# sensores_y_actuadores.net
KiCad netlist of a schematic drawn in EAGLE
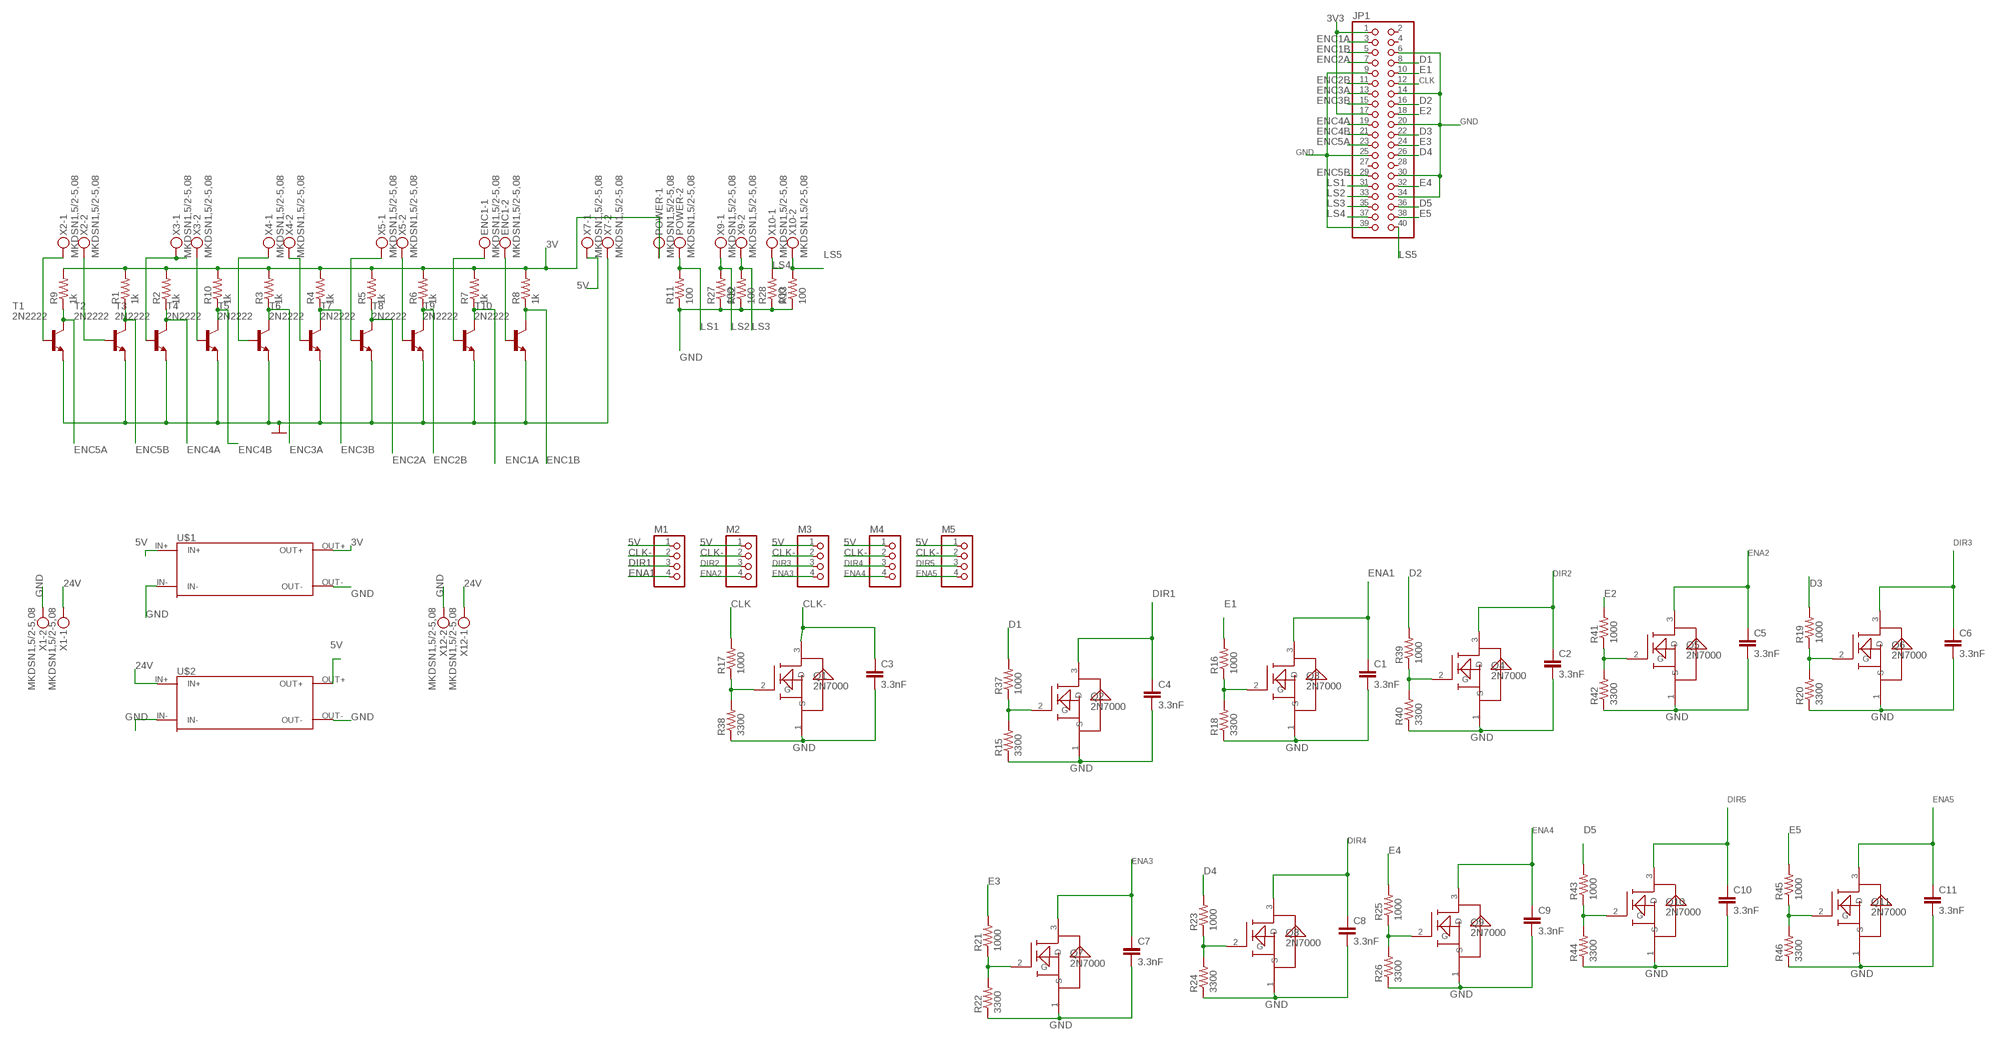
[diagram p0: schematic, sheet 1]

(export (version "E")
  (design (tool "Eeschema 10.0.6"))
  (components
    (comp (ref "C1")
      (value "3.3nF")
      (footprint "eagle-import:C025-024X044")
      (libsource (lib "eagle-import") (part "C-EU025-024X044"))
    )
    (comp (ref "C2")
      (value "3.3nF")
      (footprint "eagle-import:C025-024X044")
      (libsource (lib "eagle-import") (part "C-EU025-024X044"))
    )
    (comp (ref "C3")
      (value "3.3nF")
      (footprint "eagle-import:C025-024X044")
      (libsource (lib "eagle-import") (part "C-EU025-024X044"))
    )
    (comp (ref "C4")
      (value "3.3nF")
      (footprint "eagle-import:C025-024X044")
      (libsource (lib "eagle-import") (part "C-EU025-024X044"))
    )
    (comp (ref "C5")
      (value "3.3nF")
      (footprint "eagle-import:C025-024X044")
      (libsource (lib "eagle-import") (part "C-EU025-024X044"))
    )
    (comp (ref "C6")
      (value "3.3nF")
      (footprint "eagle-import:C025-024X044")
      (libsource (lib "eagle-import") (part "C-EU025-024X044"))
    )
    (comp (ref "C7")
      (value "3.3nF")
      (footprint "eagle-import:C025-024X044")
      (libsource (lib "eagle-import") (part "C-EU025-024X044"))
    )
    (comp (ref "C8")
      (value "3.3nF")
      (footprint "eagle-import:C025-024X044")
      (libsource (lib "eagle-import") (part "C-EU025-024X044"))
    )
    (comp (ref "C9")
      (value "3.3nF")
      (footprint "eagle-import:C025-024X044")
      (libsource (lib "eagle-import") (part "C-EU025-024X044"))
    )
    (comp (ref "C10")
      (value "3.3nF")
      (footprint "eagle-import:C025-024X044")
      (libsource (lib "eagle-import") (part "C-EU025-024X044"))
    )
    (comp (ref "C11")
      (value "3.3nF")
      (footprint "eagle-import:C025-024X044")
      (libsource (lib "eagle-import") (part "C-EU025-024X044"))
    )
    (comp (ref "ENC1")
      (value "MKDSN1,5/2-5,08")
      (footprint "eagle-import:MKDSN1,5_2-5,08")
      (libsource (lib "eagle-import") (part "MKDSN1,5/2-5,08"))
    )
    (comp (ref "JP1")
      (value "PINHD-2X20")
      (footprint "eagle-import:2X20")
      (libsource (lib "eagle-import") (part "PINHD-2X20"))
    )
    (comp (ref "M1")
      (value "PINHD-1X4")
      (footprint "eagle-import:1X04")
      (libsource (lib "eagle-import") (part "PINHD-1X4"))
    )
    (comp (ref "M2")
      (value "PINHD-1X4")
      (footprint "eagle-import:1X04")
      (libsource (lib "eagle-import") (part "PINHD-1X4"))
    )
    (comp (ref "M3")
      (value "PINHD-1X4")
      (footprint "eagle-import:1X04")
      (libsource (lib "eagle-import") (part "PINHD-1X4"))
    )
    (comp (ref "M4")
      (value "PINHD-1X4")
      (footprint "eagle-import:1X04")
      (libsource (lib "eagle-import") (part "PINHD-1X4"))
    )
    (comp (ref "M5")
      (value "PINHD-1X4")
      (footprint "eagle-import:1X04")
      (libsource (lib "eagle-import") (part "PINHD-1X4"))
    )
    (comp (ref "POWER")
      (value "MKDSN1,5/2-5,08")
      (footprint "eagle-import:MKDSN1,5_2-5,08")
      (libsource (lib "eagle-import") (part "MKDSN1,5/2-5,08"))
    )
    (comp (ref "Q1")
      (value "2N7000")
      (footprint "eagle-import:2N7000")
      (libsource (lib "eagle-import") (part "2N7000"))
    )
    (comp (ref "Q2")
      (value "2N7000")
      (footprint "eagle-import:2N7000")
      (libsource (lib "eagle-import") (part "2N7000"))
    )
    (comp (ref "Q3")
      (value "2N7000")
      (footprint "eagle-import:2N7000")
      (libsource (lib "eagle-import") (part "2N7000"))
    )
    (comp (ref "Q4")
      (value "2N7000")
      (footprint "eagle-import:2N7000")
      (libsource (lib "eagle-import") (part "2N7000"))
    )
    (comp (ref "Q5")
      (value "2N7000")
      (footprint "eagle-import:2N7000")
      (libsource (lib "eagle-import") (part "2N7000"))
    )
    (comp (ref "Q6")
      (value "2N7000")
      (footprint "eagle-import:2N7000")
      (libsource (lib "eagle-import") (part "2N7000"))
    )
    (comp (ref "Q7")
      (value "2N7000")
      (footprint "eagle-import:2N7000")
      (libsource (lib "eagle-import") (part "2N7000"))
    )
    (comp (ref "Q8")
      (value "2N7000")
      (footprint "eagle-import:2N7000")
      (libsource (lib "eagle-import") (part "2N7000"))
    )
    (comp (ref "Q9")
      (value "2N7000")
      (footprint "eagle-import:2N7000")
      (libsource (lib "eagle-import") (part "2N7000"))
    )
    (comp (ref "Q10")
      (value "2N7000")
      (footprint "eagle-import:2N7000")
      (libsource (lib "eagle-import") (part "2N7000"))
    )
    (comp (ref "Q11")
      (value "2N7000")
      (footprint "eagle-import:2N7000")
      (libsource (lib "eagle-import") (part "2N7000"))
    )
    (comp (ref "R1")
      (value "1k")
      (footprint "eagle-import:0207_10")
      (libsource (lib "eagle-import") (part "R-US_0207/10"))
    )
    (comp (ref "R2")
      (value "1k")
      (footprint "eagle-import:0207_10")
      (libsource (lib "eagle-import") (part "R-US_0207/10"))
    )
    (comp (ref "R3")
      (value "1k")
      (footprint "eagle-import:0207_10")
      (libsource (lib "eagle-import") (part "R-US_0207/10"))
    )
    (comp (ref "R4")
      (value "1k")
      (footprint "eagle-import:0207_10")
      (libsource (lib "eagle-import") (part "R-US_0207/10"))
    )
    (comp (ref "R5")
      (value "1k")
      (footprint "eagle-import:0207_10")
      (libsource (lib "eagle-import") (part "R-US_0207/10"))
    )
    (comp (ref "R6")
      (value "1k")
      (footprint "eagle-import:0207_10")
      (libsource (lib "eagle-import") (part "R-US_0207/10"))
    )
    (comp (ref "R7")
      (value "1k")
      (footprint "eagle-import:0207_10")
      (libsource (lib "eagle-import") (part "R-US_0207/10"))
    )
    (comp (ref "R8")
      (value "1k")
      (footprint "eagle-import:0207_10")
      (libsource (lib "eagle-import") (part "R-US_0207/10"))
    )
    (comp (ref "R9")
      (value "1k")
      (footprint "eagle-import:0207_10")
      (libsource (lib "eagle-import") (part "R-US_0207/10"))
    )
    (comp (ref "R10")
      (value "1k")
      (footprint "eagle-import:0207_10")
      (libsource (lib "eagle-import") (part "R-US_0207/10"))
    )
    (comp (ref "R11")
      (value "100")
      (footprint "eagle-import:0207_10")
      (libsource (lib "eagle-import") (part "R-US_0207/10"))
    )
    (comp (ref "R12")
      (value "100")
      (footprint "eagle-import:0207_10")
      (libsource (lib "eagle-import") (part "R-US_0207/10"))
    )
    (comp (ref "R13")
      (value "100")
      (footprint "eagle-import:0207_10")
      (libsource (lib "eagle-import") (part "R-US_0207/10"))
    )
    (comp (ref "R15")
      (value "3300")
      (footprint "eagle-import:0207_10")
      (libsource (lib "eagle-import") (part "R-US_0207/10"))
    )
    (comp (ref "R16")
      (value "1000")
      (footprint "eagle-import:0207_10")
      (libsource (lib "eagle-import") (part "R-US_0207/10"))
    )
    (comp (ref "R17")
      (value "1000")
      (footprint "eagle-import:0207_10")
      (libsource (lib "eagle-import") (part "R-US_0207/10"))
    )
    (comp (ref "R18")
      (value "3300")
      (footprint "eagle-import:0207_10")
      (libsource (lib "eagle-import") (part "R-US_0207/10"))
    )
    (comp (ref "R19")
      (value "1000")
      (footprint "eagle-import:0207_10")
      (libsource (lib "eagle-import") (part "R-US_0207/10"))
    )
    (comp (ref "R20")
      (value "3300")
      (footprint "eagle-import:0207_10")
      (libsource (lib "eagle-import") (part "R-US_0207/10"))
    )
    (comp (ref "R21")
      (value "1000")
      (footprint "eagle-import:0207_10")
      (libsource (lib "eagle-import") (part "R-US_0207/10"))
    )
    (comp (ref "R22")
      (value "3300")
      (footprint "eagle-import:0207_10")
      (libsource (lib "eagle-import") (part "R-US_0207/10"))
    )
    (comp (ref "R23")
      (value "1000")
      (footprint "eagle-import:0207_10")
      (libsource (lib "eagle-import") (part "R-US_0207/10"))
    )
    (comp (ref "R24")
      (value "3300")
      (footprint "eagle-import:0207_10")
      (libsource (lib "eagle-import") (part "R-US_0207/10"))
    )
    (comp (ref "R25")
      (value "1000")
      (footprint "eagle-import:0207_10")
      (libsource (lib "eagle-import") (part "R-US_0207/10"))
    )
    (comp (ref "R26")
      (value "3300")
      (footprint "eagle-import:0207_10")
      (libsource (lib "eagle-import") (part "R-US_0207/10"))
    )
    (comp (ref "R27")
      (value "100")
      (footprint "eagle-import:0207_10")
      (libsource (lib "eagle-import") (part "R-US_0207/10"))
    )
    (comp (ref "R28")
      (value "100")
      (footprint "eagle-import:0207_10")
      (libsource (lib "eagle-import") (part "R-US_0207/10"))
    )
    (comp (ref "R37")
      (value "1000")
      (footprint "eagle-import:0207_10")
      (libsource (lib "eagle-import") (part "R-US_0207/10"))
    )
    (comp (ref "R38")
      (value "3300")
      (footprint "eagle-import:0207_10")
      (libsource (lib "eagle-import") (part "R-US_0207/10"))
    )
    (comp (ref "R39")
      (value "1000")
      (footprint "eagle-import:0207_10")
      (libsource (lib "eagle-import") (part "R-US_0207/10"))
    )
    (comp (ref "R40")
      (value "3300")
      (footprint "eagle-import:0207_10")
      (libsource (lib "eagle-import") (part "R-US_0207/10"))
    )
    (comp (ref "R41")
      (value "1000")
      (footprint "eagle-import:0207_10")
      (libsource (lib "eagle-import") (part "R-US_0207/10"))
    )
    (comp (ref "R42")
      (value "3300")
      (footprint "eagle-import:0207_10")
      (libsource (lib "eagle-import") (part "R-US_0207/10"))
    )
    (comp (ref "R43")
      (value "1000")
      (footprint "eagle-import:0207_10")
      (libsource (lib "eagle-import") (part "R-US_0207/10"))
    )
    (comp (ref "R44")
      (value "3300")
      (footprint "eagle-import:0207_10")
      (libsource (lib "eagle-import") (part "R-US_0207/10"))
    )
    (comp (ref "R45")
      (value "1000")
      (footprint "eagle-import:0207_10")
      (libsource (lib "eagle-import") (part "R-US_0207/10"))
    )
    (comp (ref "R46")
      (value "3300")
      (footprint "eagle-import:0207_10")
      (libsource (lib "eagle-import") (part "R-US_0207/10"))
    )
    (comp (ref "T1")
      (value "2N2222")
      (footprint "eagle-import:2N2222")
      (libsource (lib "eagle-import") (part "2N2222"))
    )
    (comp (ref "T2")
      (value "2N2222")
      (footprint "eagle-import:2N2222")
      (libsource (lib "eagle-import") (part "2N2222"))
    )
    (comp (ref "T3")
      (value "2N2222")
      (footprint "eagle-import:2N2222")
      (libsource (lib "eagle-import") (part "2N2222"))
    )
    (comp (ref "T4")
      (value "2N2222")
      (footprint "eagle-import:2N2222")
      (libsource (lib "eagle-import") (part "2N2222"))
    )
    (comp (ref "T5")
      (value "2N2222")
      (footprint "eagle-import:2N2222")
      (libsource (lib "eagle-import") (part "2N2222"))
    )
    (comp (ref "T6")
      (value "2N2222")
      (footprint "eagle-import:2N2222")
      (libsource (lib "eagle-import") (part "2N2222"))
    )
    (comp (ref "T7")
      (value "2N2222")
      (footprint "eagle-import:2N2222")
      (libsource (lib "eagle-import") (part "2N2222"))
    )
    (comp (ref "T8")
      (value "2N2222")
      (footprint "eagle-import:2N2222")
      (libsource (lib "eagle-import") (part "2N2222"))
    )
    (comp (ref "T9")
      (value "2N2222")
      (footprint "eagle-import:2N2222")
      (libsource (lib "eagle-import") (part "2N2222"))
    )
    (comp (ref "T10")
      (value "2N2222")
      (footprint "eagle-import:2N2222")
      (libsource (lib "eagle-import") (part "2N2222"))
    )
    (comp (ref "U$1")
      (value "LM2596")
      (footprint "eagle-import:LM2596")
      (libsource (lib "eagle-import") (part "LM2596"))
    )
    (comp (ref "U$2")
      (value "LM2596")
      (footprint "eagle-import:LM2596")
      (libsource (lib "eagle-import") (part "LM2596"))
    )
    (comp (ref "X1")
      (value "MKDSN1,5/2-5,08")
      (footprint "eagle-import:MKDSN1,5_2-5,08")
      (libsource (lib "eagle-import") (part "MKDSN1,5/2-5,08"))
    )
    (comp (ref "X2")
      (value "MKDSN1,5/2-5,08")
      (footprint "eagle-import:MKDSN1,5_2-5,08")
      (libsource (lib "eagle-import") (part "MKDSN1,5/2-5,08"))
    )
    (comp (ref "X3")
      (value "MKDSN1,5/2-5,08")
      (footprint "eagle-import:MKDSN1,5_2-5,08")
      (libsource (lib "eagle-import") (part "MKDSN1,5/2-5,08"))
    )
    (comp (ref "X4")
      (value "MKDSN1,5/2-5,08")
      (footprint "eagle-import:MKDSN1,5_2-5,08")
      (libsource (lib "eagle-import") (part "MKDSN1,5/2-5,08"))
    )
    (comp (ref "X5")
      (value "MKDSN1,5/2-5,08")
      (footprint "eagle-import:MKDSN1,5_2-5,08")
      (libsource (lib "eagle-import") (part "MKDSN1,5/2-5,08"))
    )
    (comp (ref "X7")
      (value "MKDSN1,5/2-5,08")
      (footprint "eagle-import:MKDSN1,5_2-5,08")
      (libsource (lib "eagle-import") (part "MKDSN1,5/2-5,08"))
    )
    (comp (ref "X9")
      (value "MKDSN1,5/2-5,08")
      (footprint "eagle-import:MKDSN1,5_2-5,08")
      (libsource (lib "eagle-import") (part "MKDSN1,5/2-5,08"))
    )
    (comp (ref "X10")
      (value "MKDSN1,5/2-5,08")
      (footprint "eagle-import:MKDSN1,5_2-5,08")
      (libsource (lib "eagle-import") (part "MKDSN1,5/2-5,08"))
    )
    (comp (ref "X12")
      (value "MKDSN1,5/2-5,08")
      (footprint "eagle-import:MKDSN1,5_2-5,08")
      (libsource (lib "eagle-import") (part "MKDSN1,5/2-5,08"))
    )
  )
  (nets
    (net (code "1") (name "/3V") (class "Default")
      (node (ref "POWER") (pin "1") (pinfunction "KL_1") (pintype "passive"))
      (node (ref "R1") (pin "2") (pinfunction "2_2") (pintype "passive"))
      (node (ref "R10") (pin "2") (pinfunction "2_2") (pintype "passive"))
      (node (ref "R2") (pin "2") (pinfunction "2_2") (pintype "passive"))
      (node (ref "R3") (pin "2") (pinfunction "2_2") (pintype "passive"))
      (node (ref "R4") (pin "2") (pinfunction "2_2") (pintype "passive"))
      (node (ref "R5") (pin "2") (pinfunction "2_2") (pintype "passive"))
      (node (ref "R6") (pin "2") (pinfunction "2_2") (pintype "passive"))
      (node (ref "R7") (pin "2") (pinfunction "2_2") (pintype "passive"))
      (node (ref "R8") (pin "2") (pinfunction "2_2") (pintype "passive"))
      (node (ref "R9") (pin "2") (pinfunction "2_2") (pintype "passive"))
      (node (ref "U$1") (pin "OUT+") (pinfunction "OUT+_OUT+") (pintype "bidirectional"))
    )
    (net (code "2") (name "/3V3") (class "Default")
      (node (ref "JP1") (pin "1") (pinfunction "1_1") (pintype "passive"))
      (node (ref "JP1") (pin "17") (pinfunction "17_17") (pintype "passive"))
    )
    (net (code "3") (name "/5V") (class "Default")
      (node (ref "M1") (pin "1") (pinfunction "1_1") (pintype "passive"))
      (node (ref "M2") (pin "1") (pinfunction "1_1") (pintype "passive"))
      (node (ref "M3") (pin "1") (pinfunction "1_1") (pintype "passive"))
      (node (ref "M4") (pin "1") (pinfunction "1_1") (pintype "passive"))
      (node (ref "M5") (pin "1") (pinfunction "1_1") (pintype "passive"))
      (node (ref "U$1") (pin "IN+") (pinfunction "IN+_IN+") (pintype "bidirectional"))
      (node (ref "U$2") (pin "OUT+") (pinfunction "OUT+_OUT+") (pintype "bidirectional"))
      (node (ref "X7") (pin "1") (pinfunction "KL_1") (pintype "passive"))
    )
    (net (code "4") (name "/24V") (class "Default")
      (node (ref "U$2") (pin "IN+") (pinfunction "IN+_IN+") (pintype "bidirectional"))
      (node (ref "X1") (pin "1") (pinfunction "KL_1") (pintype "passive"))
      (node (ref "X12") (pin "1") (pinfunction "KL_1") (pintype "passive"))
    )
    (net (code "5") (name "/CLK") (class "Default")
      (node (ref "JP1") (pin "12") (pinfunction "12_12") (pintype "passive"))
      (node (ref "R17") (pin "2") (pinfunction "2_2") (pintype "passive"))
    )
    (net (code "6") (name "/CLK-") (class "Default")
      (node (ref "C3") (pin "1") (pinfunction "1_1") (pintype "passive"))
      (node (ref "M1") (pin "2") (pinfunction "2_2") (pintype "passive"))
      (node (ref "M2") (pin "2") (pinfunction "2_2") (pintype "passive"))
      (node (ref "M3") (pin "2") (pinfunction "2_2") (pintype "passive"))
      (node (ref "M4") (pin "2") (pinfunction "2_2") (pintype "passive"))
      (node (ref "M5") (pin "2") (pinfunction "2_2") (pintype "passive"))
      (node (ref "Q1") (pin "3") (pinfunction "D_3") (pintype "bidirectional"))
    )
    (net (code "7") (name "/D1") (class "Default")
      (node (ref "JP1") (pin "8") (pinfunction "8_8") (pintype "passive"))
      (node (ref "R37") (pin "2") (pinfunction "2_2") (pintype "passive"))
    )
    (net (code "8") (name "/D2") (class "Default")
      (node (ref "JP1") (pin "16") (pinfunction "16_16") (pintype "passive"))
      (node (ref "R39") (pin "2") (pinfunction "2_2") (pintype "passive"))
    )
    (net (code "9") (name "/D3") (class "Default")
      (node (ref "JP1") (pin "22") (pinfunction "22_22") (pintype "passive"))
      (node (ref "R19") (pin "2") (pinfunction "2_2") (pintype "passive"))
    )
    (net (code "10") (name "/D4") (class "Default")
      (node (ref "JP1") (pin "26") (pinfunction "26_26") (pintype "passive"))
      (node (ref "R23") (pin "2") (pinfunction "2_2") (pintype "passive"))
    )
    (net (code "11") (name "/D5") (class "Default")
      (node (ref "JP1") (pin "36") (pinfunction "36_36") (pintype "passive"))
      (node (ref "R43") (pin "2") (pinfunction "2_2") (pintype "passive"))
    )
    (net (code "12") (name "/DIR1") (class "Default")
      (node (ref "C4") (pin "1") (pinfunction "1_1") (pintype "passive"))
      (node (ref "M1") (pin "3") (pinfunction "3_3") (pintype "passive"))
      (node (ref "Q2") (pin "3") (pinfunction "D_3") (pintype "bidirectional"))
    )
    (net (code "13") (name "/DIR2") (class "Default")
      (node (ref "C2") (pin "1") (pinfunction "1_1") (pintype "passive"))
      (node (ref "M2") (pin "3") (pinfunction "3_3") (pintype "passive"))
      (node (ref "Q4") (pin "3") (pinfunction "D_3") (pintype "bidirectional"))
    )
    (net (code "14") (name "/DIR3") (class "Default")
      (node (ref "C6") (pin "1") (pinfunction "1_1") (pintype "passive"))
      (node (ref "M3") (pin "3") (pinfunction "3_3") (pintype "passive"))
      (node (ref "Q6") (pin "3") (pinfunction "D_3") (pintype "bidirectional"))
    )
    (net (code "15") (name "/DIR4") (class "Default")
      (node (ref "C8") (pin "1") (pinfunction "1_1") (pintype "passive"))
      (node (ref "M4") (pin "3") (pinfunction "3_3") (pintype "passive"))
      (node (ref "Q8") (pin "3") (pinfunction "D_3") (pintype "bidirectional"))
    )
    (net (code "16") (name "/DIR5") (class "Default")
      (node (ref "C10") (pin "1") (pinfunction "1_1") (pintype "passive"))
      (node (ref "M5") (pin "3") (pinfunction "3_3") (pintype "passive"))
      (node (ref "Q10") (pin "3") (pinfunction "D_3") (pintype "bidirectional"))
    )
    (net (code "17") (name "/E1") (class "Default")
      (node (ref "JP1") (pin "10") (pinfunction "10_10") (pintype "passive"))
      (node (ref "R16") (pin "2") (pinfunction "2_2") (pintype "passive"))
    )
    (net (code "18") (name "/E2") (class "Default")
      (node (ref "JP1") (pin "18") (pinfunction "18_18") (pintype "passive"))
      (node (ref "R41") (pin "2") (pinfunction "2_2") (pintype "passive"))
    )
    (net (code "19") (name "/E3") (class "Default")
      (node (ref "JP1") (pin "24") (pinfunction "24_24") (pintype "passive"))
      (node (ref "R21") (pin "2") (pinfunction "2_2") (pintype "passive"))
    )
    (net (code "20") (name "/E4") (class "Default")
      (node (ref "JP1") (pin "32") (pinfunction "32_32") (pintype "passive"))
      (node (ref "R25") (pin "2") (pinfunction "2_2") (pintype "passive"))
    )
    (net (code "21") (name "/E5") (class "Default")
      (node (ref "JP1") (pin "38") (pinfunction "38_38") (pintype "passive"))
      (node (ref "R45") (pin "2") (pinfunction "2_2") (pintype "passive"))
    )
    (net (code "22") (name "/ENA1") (class "Default")
      (node (ref "C1") (pin "1") (pinfunction "1_1") (pintype "passive"))
      (node (ref "M1") (pin "4") (pinfunction "4_4") (pintype "passive"))
      (node (ref "Q3") (pin "3") (pinfunction "D_3") (pintype "bidirectional"))
    )
    (net (code "23") (name "/ENA2") (class "Default")
      (node (ref "C5") (pin "1") (pinfunction "1_1") (pintype "passive"))
      (node (ref "M2") (pin "4") (pinfunction "4_4") (pintype "passive"))
      (node (ref "Q5") (pin "3") (pinfunction "D_3") (pintype "bidirectional"))
    )
    (net (code "24") (name "/ENA3") (class "Default")
      (node (ref "C7") (pin "1") (pinfunction "1_1") (pintype "passive"))
      (node (ref "M3") (pin "4") (pinfunction "4_4") (pintype "passive"))
      (node (ref "Q7") (pin "3") (pinfunction "D_3") (pintype "bidirectional"))
    )
    (net (code "25") (name "/ENA4") (class "Default")
      (node (ref "C9") (pin "1") (pinfunction "1_1") (pintype "passive"))
      (node (ref "M4") (pin "4") (pinfunction "4_4") (pintype "passive"))
      (node (ref "Q9") (pin "3") (pinfunction "D_3") (pintype "bidirectional"))
    )
    (net (code "26") (name "/ENA5") (class "Default")
      (node (ref "C11") (pin "1") (pinfunction "1_1") (pintype "passive"))
      (node (ref "M5") (pin "4") (pinfunction "4_4") (pintype "passive"))
      (node (ref "Q11") (pin "3") (pinfunction "D_3") (pintype "bidirectional"))
    )
    (net (code "27") (name "/ENC1A") (class "Default")
      (node (ref "JP1") (pin "3") (pinfunction "3_3") (pintype "passive"))
      (node (ref "R7") (pin "1") (pinfunction "1_1") (pintype "passive"))
      (node (ref "T9") (pin "C") (pinfunction "C_C") (pintype "passive"))
    )
    (net (code "28") (name "/ENC1B") (class "Default")
      (node (ref "JP1") (pin "5") (pinfunction "5_5") (pintype "passive"))
      (node (ref "R8") (pin "1") (pinfunction "1_1") (pintype "passive"))
      (node (ref "T10") (pin "C") (pinfunction "C_C") (pintype "passive"))
    )
    (net (code "29") (name "/ENC2A") (class "Default")
      (node (ref "JP1") (pin "7") (pinfunction "7_7") (pintype "passive"))
      (node (ref "R5") (pin "1") (pinfunction "1_1") (pintype "passive"))
      (node (ref "T7") (pin "C") (pinfunction "C_C") (pintype "passive"))
    )
    (net (code "30") (name "/ENC2B") (class "Default")
      (node (ref "JP1") (pin "11") (pinfunction "11_11") (pintype "passive"))
      (node (ref "R6") (pin "1") (pinfunction "1_1") (pintype "passive"))
      (node (ref "T8") (pin "C") (pinfunction "C_C") (pintype "passive"))
    )
    (net (code "31") (name "/ENC3A") (class "Default")
      (node (ref "JP1") (pin "13") (pinfunction "13_13") (pintype "passive"))
      (node (ref "R3") (pin "1") (pinfunction "1_1") (pintype "passive"))
      (node (ref "T5") (pin "C") (pinfunction "C_C") (pintype "passive"))
    )
    (net (code "32") (name "/ENC3B") (class "Default")
      (node (ref "JP1") (pin "15") (pinfunction "15_15") (pintype "passive"))
      (node (ref "R4") (pin "1") (pinfunction "1_1") (pintype "passive"))
      (node (ref "T6") (pin "C") (pinfunction "C_C") (pintype "passive"))
    )
    (net (code "33") (name "/ENC4A") (class "Default")
      (node (ref "JP1") (pin "19") (pinfunction "19_19") (pintype "passive"))
      (node (ref "R2") (pin "1") (pinfunction "1_1") (pintype "passive"))
      (node (ref "T3") (pin "C") (pinfunction "C_C") (pintype "passive"))
    )
    (net (code "34") (name "/ENC4B") (class "Default")
      (node (ref "JP1") (pin "21") (pinfunction "21_21") (pintype "passive"))
      (node (ref "R10") (pin "1") (pinfunction "1_1") (pintype "passive"))
      (node (ref "T4") (pin "C") (pinfunction "C_C") (pintype "passive"))
    )
    (net (code "35") (name "/ENC5A") (class "Default")
      (node (ref "JP1") (pin "23") (pinfunction "23_23") (pintype "passive"))
      (node (ref "R9") (pin "1") (pinfunction "1_1") (pintype "passive"))
      (node (ref "T1") (pin "C") (pinfunction "C_C") (pintype "passive"))
    )
    (net (code "36") (name "/ENC5B") (class "Default")
      (node (ref "JP1") (pin "29") (pinfunction "29_29") (pintype "passive"))
      (node (ref "R1") (pin "1") (pinfunction "1_1") (pintype "passive"))
      (node (ref "T2") (pin "C") (pinfunction "C_C") (pintype "passive"))
    )
    (net (code "37") (name "/LS1") (class "Default")
      (node (ref "JP1") (pin "31") (pinfunction "31_31") (pintype "passive"))
      (node (ref "POWER") (pin "2") (pinfunction "KL_2") (pintype "passive"))
      (node (ref "R11") (pin "2") (pinfunction "2_2") (pintype "passive"))
    )
    (net (code "38") (name "/LS2") (class "Default")
      (node (ref "JP1") (pin "33") (pinfunction "33_33") (pintype "passive"))
      (node (ref "R27") (pin "2") (pinfunction "2_2") (pintype "passive"))
      (node (ref "X9") (pin "1") (pinfunction "KL_1") (pintype "passive"))
    )
    (net (code "39") (name "/LS3") (class "Default")
      (node (ref "JP1") (pin "35") (pinfunction "35_35") (pintype "passive"))
      (node (ref "R12") (pin "2") (pinfunction "2_2") (pintype "passive"))
      (node (ref "X9") (pin "2") (pinfunction "KL_2") (pintype "passive"))
    )
    (net (code "40") (name "/LS4") (class "Default")
      (node (ref "JP1") (pin "37") (pinfunction "37_37") (pintype "passive"))
      (node (ref "R28") (pin "2") (pinfunction "2_2") (pintype "passive"))
      (node (ref "X10") (pin "1") (pinfunction "KL_1") (pintype "passive"))
    )
    (net (code "41") (name "/LS5") (class "Default")
      (node (ref "JP1") (pin "40") (pinfunction "40_40") (pintype "passive"))
      (node (ref "R13") (pin "2") (pinfunction "2_2") (pintype "passive"))
      (node (ref "X10") (pin "2") (pinfunction "KL_2") (pintype "passive"))
    )
    (net (code "42") (name "GND") (class "Default")
      (node (ref "C1") (pin "2") (pinfunction "2_2") (pintype "passive"))
      (node (ref "C10") (pin "2") (pinfunction "2_2") (pintype "passive"))
      (node (ref "C11") (pin "2") (pinfunction "2_2") (pintype "passive"))
      (node (ref "C2") (pin "2") (pinfunction "2_2") (pintype "passive"))
      (node (ref "C3") (pin "2") (pinfunction "2_2") (pintype "passive"))
      (node (ref "C4") (pin "2") (pinfunction "2_2") (pintype "passive"))
      (node (ref "C5") (pin "2") (pinfunction "2_2") (pintype "passive"))
      (node (ref "C6") (pin "2") (pinfunction "2_2") (pintype "passive"))
      (node (ref "C7") (pin "2") (pinfunction "2_2") (pintype "passive"))
      (node (ref "C8") (pin "2") (pinfunction "2_2") (pintype "passive"))
      (node (ref "C9") (pin "2") (pinfunction "2_2") (pintype "passive"))
      (node (ref "JP1") (pin "14") (pinfunction "14_14") (pintype "passive"))
      (node (ref "JP1") (pin "20") (pinfunction "20_20") (pintype "passive"))
      (node (ref "JP1") (pin "25") (pinfunction "25_25") (pintype "passive"))
      (node (ref "JP1") (pin "30") (pinfunction "30_30") (pintype "passive"))
      (node (ref "JP1") (pin "34") (pinfunction "34_34") (pintype "passive"))
      (node (ref "JP1") (pin "39") (pinfunction "39_39") (pintype "passive"))
      (node (ref "JP1") (pin "6") (pinfunction "6_6") (pintype "passive"))
      (node (ref "JP1") (pin "9") (pinfunction "9_9") (pintype "passive"))
      (node (ref "Q1") (pin "1") (pinfunction "S_1") (pintype "bidirectional"))
      (node (ref "Q10") (pin "1") (pinfunction "S_1") (pintype "bidirectional"))
      (node (ref "Q11") (pin "1") (pinfunction "S_1") (pintype "bidirectional"))
      (node (ref "Q2") (pin "1") (pinfunction "S_1") (pintype "bidirectional"))
      (node (ref "Q3") (pin "1") (pinfunction "S_1") (pintype "bidirectional"))
      (node (ref "Q4") (pin "1") (pinfunction "S_1") (pintype "bidirectional"))
      (node (ref "Q5") (pin "1") (pinfunction "S_1") (pintype "bidirectional"))
      (node (ref "Q6") (pin "1") (pinfunction "S_1") (pintype "bidirectional"))
      (node (ref "Q7") (pin "1") (pinfunction "S_1") (pintype "bidirectional"))
      (node (ref "Q8") (pin "1") (pinfunction "S_1") (pintype "bidirectional"))
      (node (ref "Q9") (pin "1") (pinfunction "S_1") (pintype "bidirectional"))
      (node (ref "R11") (pin "1") (pinfunction "1_1") (pintype "passive"))
      (node (ref "R12") (pin "1") (pinfunction "1_1") (pintype "passive"))
      (node (ref "R13") (pin "1") (pinfunction "1_1") (pintype "passive"))
      (node (ref "R15") (pin "1") (pinfunction "1_1") (pintype "passive"))
      (node (ref "R18") (pin "1") (pinfunction "1_1") (pintype "passive"))
      (node (ref "R20") (pin "1") (pinfunction "1_1") (pintype "passive"))
      (node (ref "R22") (pin "1") (pinfunction "1_1") (pintype "passive"))
      (node (ref "R24") (pin "1") (pinfunction "1_1") (pintype "passive"))
      (node (ref "R26") (pin "1") (pinfunction "1_1") (pintype "passive"))
      (node (ref "R27") (pin "1") (pinfunction "1_1") (pintype "passive"))
      (node (ref "R28") (pin "1") (pinfunction "1_1") (pintype "passive"))
      (node (ref "R38") (pin "1") (pinfunction "1_1") (pintype "passive"))
      (node (ref "R40") (pin "1") (pinfunction "1_1") (pintype "passive"))
      (node (ref "R42") (pin "1") (pinfunction "1_1") (pintype "passive"))
      (node (ref "R44") (pin "1") (pinfunction "1_1") (pintype "passive"))
      (node (ref "R46") (pin "1") (pinfunction "1_1") (pintype "passive"))
      (node (ref "T1") (pin "E") (pinfunction "E_E") (pintype "passive"))
      (node (ref "T10") (pin "E") (pinfunction "E_E") (pintype "passive"))
      (node (ref "T2") (pin "E") (pinfunction "E_E") (pintype "passive"))
      (node (ref "T3") (pin "E") (pinfunction "E_E") (pintype "passive"))
      (node (ref "T4") (pin "E") (pinfunction "E_E") (pintype "passive"))
      (node (ref "T5") (pin "E") (pinfunction "E_E") (pintype "passive"))
      (node (ref "T6") (pin "E") (pinfunction "E_E") (pintype "passive"))
      (node (ref "T7") (pin "E") (pinfunction "E_E") (pintype "passive"))
      (node (ref "T8") (pin "E") (pinfunction "E_E") (pintype "passive"))
      (node (ref "T9") (pin "E") (pinfunction "E_E") (pintype "passive"))
      (node (ref "U$1") (pin "IN-") (pinfunction "IN-_IN-") (pintype "bidirectional"))
      (node (ref "U$1") (pin "OUT-") (pinfunction "OUT-_OUT-") (pintype "bidirectional"))
      (node (ref "U$2") (pin "IN-") (pinfunction "IN-_IN-") (pintype "bidirectional"))
      (node (ref "U$2") (pin "OUT-") (pinfunction "OUT-_OUT-") (pintype "bidirectional"))
      (node (ref "X1") (pin "2") (pinfunction "KL_2") (pintype "passive"))
      (node (ref "X12") (pin "2") (pinfunction "KL_2") (pintype "passive"))
      (node (ref "X7") (pin "2") (pinfunction "KL_2") (pintype "passive"))
    )
    (net (code "43") (name "Net-(ENC1A-KL)") (class "Default")
      (node (ref "ENC1") (pin "1") (pinfunction "KL_1") (pintype "passive"))
      (node (ref "T9") (pin "B") (pinfunction "B_B") (pintype "passive"))
    )
    (net (code "44") (name "Net-(ENC1B-KL)") (class "Default")
      (node (ref "ENC1") (pin "2") (pinfunction "KL_2") (pintype "passive"))
      (node (ref "T10") (pin "B") (pinfunction "B_B") (pintype "passive"))
    )
    (net (code "45") (name "Net-(Q1-G)") (class "Default")
      (node (ref "Q1") (pin "2") (pinfunction "G_2") (pintype "bidirectional"))
      (node (ref "R17") (pin "1") (pinfunction "1_1") (pintype "passive"))
      (node (ref "R38") (pin "2") (pinfunction "2_2") (pintype "passive"))
    )
    (net (code "46") (name "Net-(Q2-G)") (class "Default")
      (node (ref "Q2") (pin "2") (pinfunction "G_2") (pintype "bidirectional"))
      (node (ref "R15") (pin "2") (pinfunction "2_2") (pintype "passive"))
      (node (ref "R37") (pin "1") (pinfunction "1_1") (pintype "passive"))
    )
    (net (code "47") (name "Net-(Q3-G)") (class "Default")
      (node (ref "Q3") (pin "2") (pinfunction "G_2") (pintype "bidirectional"))
      (node (ref "R16") (pin "1") (pinfunction "1_1") (pintype "passive"))
      (node (ref "R18") (pin "2") (pinfunction "2_2") (pintype "passive"))
    )
    (net (code "48") (name "Net-(Q4-G)") (class "Default")
      (node (ref "Q4") (pin "2") (pinfunction "G_2") (pintype "bidirectional"))
      (node (ref "R39") (pin "1") (pinfunction "1_1") (pintype "passive"))
      (node (ref "R40") (pin "2") (pinfunction "2_2") (pintype "passive"))
    )
    (net (code "49") (name "Net-(Q5-G)") (class "Default")
      (node (ref "Q5") (pin "2") (pinfunction "G_2") (pintype "bidirectional"))
      (node (ref "R41") (pin "1") (pinfunction "1_1") (pintype "passive"))
      (node (ref "R42") (pin "2") (pinfunction "2_2") (pintype "passive"))
    )
    (net (code "50") (name "Net-(Q6-G)") (class "Default")
      (node (ref "Q6") (pin "2") (pinfunction "G_2") (pintype "bidirectional"))
      (node (ref "R19") (pin "1") (pinfunction "1_1") (pintype "passive"))
      (node (ref "R20") (pin "2") (pinfunction "2_2") (pintype "passive"))
    )
    (net (code "51") (name "Net-(Q7-G)") (class "Default")
      (node (ref "Q7") (pin "2") (pinfunction "G_2") (pintype "bidirectional"))
      (node (ref "R21") (pin "1") (pinfunction "1_1") (pintype "passive"))
      (node (ref "R22") (pin "2") (pinfunction "2_2") (pintype "passive"))
    )
    (net (code "52") (name "Net-(Q8-G)") (class "Default")
      (node (ref "Q8") (pin "2") (pinfunction "G_2") (pintype "bidirectional"))
      (node (ref "R23") (pin "1") (pinfunction "1_1") (pintype "passive"))
      (node (ref "R24") (pin "2") (pinfunction "2_2") (pintype "passive"))
    )
    (net (code "53") (name "Net-(Q9-G)") (class "Default")
      (node (ref "Q9") (pin "2") (pinfunction "G_2") (pintype "bidirectional"))
      (node (ref "R25") (pin "1") (pinfunction "1_1") (pintype "passive"))
      (node (ref "R26") (pin "2") (pinfunction "2_2") (pintype "passive"))
    )
    (net (code "54") (name "Net-(Q10-G)") (class "Default")
      (node (ref "Q10") (pin "2") (pinfunction "G_2") (pintype "bidirectional"))
      (node (ref "R43") (pin "1") (pinfunction "1_1") (pintype "passive"))
      (node (ref "R44") (pin "2") (pinfunction "2_2") (pintype "passive"))
    )
    (net (code "55") (name "Net-(Q11-G)") (class "Default")
      (node (ref "Q11") (pin "2") (pinfunction "G_2") (pintype "bidirectional"))
      (node (ref "R45") (pin "1") (pinfunction "1_1") (pintype "passive"))
      (node (ref "R46") (pin "2") (pinfunction "2_2") (pintype "passive"))
    )
    (net (code "56") (name "Net-(X2A-KL)") (class "Default")
      (node (ref "T1") (pin "B") (pinfunction "B_B") (pintype "passive"))
      (node (ref "X2") (pin "1") (pinfunction "KL_1") (pintype "passive"))
    )
    (net (code "57") (name "Net-(X2B-KL)") (class "Default")
      (node (ref "T2") (pin "B") (pinfunction "B_B") (pintype "passive"))
      (node (ref "X2") (pin "2") (pinfunction "KL_2") (pintype "passive"))
    )
    (net (code "58") (name "Net-(X3A-KL)") (class "Default")
      (node (ref "T3") (pin "B") (pinfunction "B_B") (pintype "passive"))
      (node (ref "X3") (pin "1") (pinfunction "KL_1") (pintype "passive"))
    )
    (net (code "59") (name "Net-(X3B-KL)") (class "Default")
      (node (ref "T4") (pin "B") (pinfunction "B_B") (pintype "passive"))
      (node (ref "X3") (pin "2") (pinfunction "KL_2") (pintype "passive"))
    )
    (net (code "60") (name "Net-(X4A-KL)") (class "Default")
      (node (ref "T5") (pin "B") (pinfunction "B_B") (pintype "passive"))
      (node (ref "X4") (pin "1") (pinfunction "KL_1") (pintype "passive"))
    )
    (net (code "61") (name "Net-(X4B-KL)") (class "Default")
      (node (ref "T6") (pin "B") (pinfunction "B_B") (pintype "passive"))
      (node (ref "X4") (pin "2") (pinfunction "KL_2") (pintype "passive"))
    )
    (net (code "62") (name "Net-(X5A-KL)") (class "Default")
      (node (ref "T7") (pin "B") (pinfunction "B_B") (pintype "passive"))
      (node (ref "X5") (pin "1") (pinfunction "KL_1") (pintype "passive"))
    )
    (net (code "63") (name "Net-(X5B-KL)") (class "Default")
      (node (ref "T8") (pin "B") (pinfunction "B_B") (pintype "passive"))
      (node (ref "X5") (pin "2") (pinfunction "KL_2") (pintype "passive"))
    )
    (net (code "64") (name "unconnected-(JP1-Pad2)") (class "Default")
      (node (ref "JP1") (pin "2") (pinfunction "2_2") (pintype "passive"))
    )
    (net (code "65") (name "unconnected-(JP1-Pad4)") (class "Default")
      (node (ref "JP1") (pin "4") (pinfunction "4_4") (pintype "passive"))
    )
    (net (code "66") (name "unconnected-(JP1-Pad27)") (class "Default")
      (node (ref "JP1") (pin "27") (pinfunction "27_27") (pintype "passive"))
    )
    (net (code "67") (name "unconnected-(JP1-Pad28)") (class "Default")
      (node (ref "JP1") (pin "28") (pinfunction "28_28") (pintype "passive"))
    )
  )
)
